# CTLR.net
KiCad netlist of a schematic drawn in Altium Designer
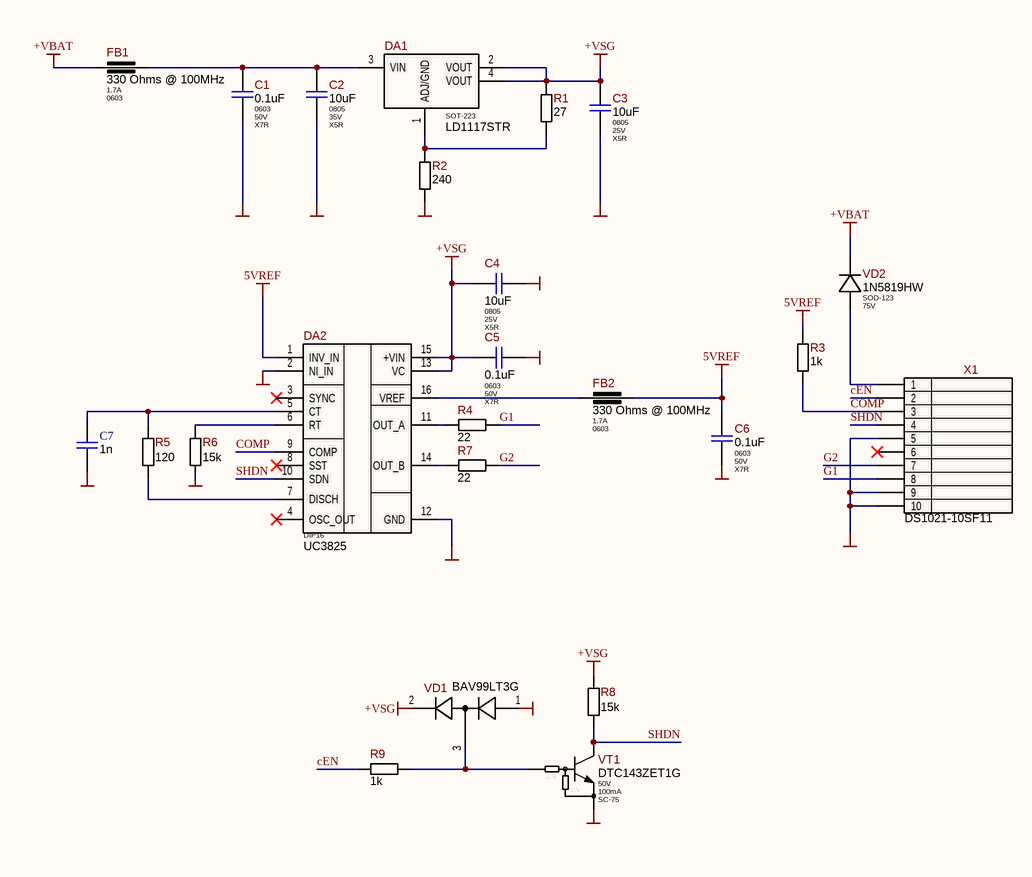
[diagram p0: CTLR.SchDoc]

(export (version "E")
  (design (tool "Eeschema 10.0.6"))
  (components
    (comp (ref "C1")
      (value "0.1uF")
      (footprint "C_CERAMIC_0603_MED")
      (description "100nF 50V X7R ±10% 0603 Ceramic Capacitor RoHS")
      (fields
        (field (name "PACKAGE") "0603")
        (field (name "VOLTAGE") "50V")
        (field (name "DIELECTRIC TYPE") "X7R")
        (field (name "PART NUMBER") "CL10B104KB8NNNC")
        (field (name "MANUFACTURER") "Samsung Electro-Mechanics")
      )
      (libsource (lib "capacitors") (part "CL10B104KB8NNNC"))
    )
    (comp (ref "C2")
      (value "10uF")
      (footprint "CAP-0805(2012)X125T20")
      (description "10uF 35V X5R ±10% 0805 Low ESL Ceramic Capacitor RoHS")
      (fields
        (field (name "PACKAGE") "0805")
        (field (name "VOLTAGE") "35V")
        (field (name "DIELECTRIC TYPE") "X5R")
        (field (name "PART NUMBER") "C2012X5R1V106K125AC")
        (field (name "MANUFACTURER") "TDK Corporation")
      )
      (libsource (lib "capacitors") (part "C2012X5R1V106K125AC"))
    )
    (comp (ref "C3")
      (value "10uF")
      (footprint "CAP-0805(2012)X85T10")
      (description "10uF 25V X5R ±20% 0805 Ceramic Capacitor RoHS")
      (fields
        (field (name "PACKAGE") "0805")
        (field (name "VOLTAGE") "25V")
        (field (name "DIELECTRIC TYPE") "X5R")
        (field (name "PART NUMBER") "C2012X5R1E106M085AC")
        (field (name "MANUFACTURER") "TDK Corporation")
      )
      (libsource (lib "capacitors") (part "C2012X5R1E106M085AC"))
    )
    (comp (ref "C4")
      (value "10uF")
      (footprint "CAP-0805(2012)X85T10")
      (description "10uF 25V X5R ±20% 0805 Ceramic Capacitor RoHS")
      (fields
        (field (name "PACKAGE") "0805")
        (field (name "VOLTAGE") "25V")
        (field (name "DIELECTRIC TYPE") "X5R")
        (field (name "PART NUMBER") "C2012X5R1E106M085AC")
        (field (name "MANUFACTURER") "TDK Corporation")
      )
      (libsource (lib "capacitors") (part "C2012X5R1E106M085AC"))
    )
    (comp (ref "C5")
      (value "0.1uF")
      (footprint "C_CERAMIC_0603_MED")
      (description "100nF 50V X7R ±10% 0603 Ceramic Capacitor RoHS")
      (fields
        (field (name "PACKAGE") "0603")
        (field (name "VOLTAGE") "50V")
        (field (name "DIELECTRIC TYPE") "X7R")
        (field (name "PART NUMBER") "CL10B104KB8NNNC")
        (field (name "MANUFACTURER") "Samsung Electro-Mechanics")
      )
      (libsource (lib "capacitors") (part "CL10B104KB8NNNC"))
    )
    (comp (ref "C6")
      (value "0.1uF")
      (footprint "C_CERAMIC_0603_MED")
      (description "100nF 50V X7R ±10% 0603 Ceramic Capacitor RoHS")
      (fields
        (field (name "PACKAGE") "0603")
        (field (name "VOLTAGE") "50V")
        (field (name "DIELECTRIC TYPE") "X7R")
        (field (name "PART NUMBER") "CL10B104KB8NNNC")
        (field (name "MANUFACTURER") "Samsung Electro-Mechanics")
      )
      (libsource (lib "capacitors") (part "CL10B104KB8NNNC"))
    )
    (comp (ref "C7")
      (value "1n")
      (footprint "CAP: MKS2 (W=2.50MM)")
      (description "Multilayer Ceramic Capacitors MLCC - SMD/SMT 10 uF 25 VDC 10% 1206 X7R")
      (fields (field (name "MANUFACTURER") "Murata") (field (name "PART NUMBER") "GRM31CR71E106KA12L"))
      (libsource (lib "vitech_capacitors") (part "CAP_NON_POLAR_THT"))
    )
    (comp (ref "DA1")
      (value "LD1117STR")
      (footprint "SOT-223")
      (description "Adjustable Low Drop Positive Voltage Regulator, 1.25V to 15V, 800mA")
      (fields
        (field (name "PACKAGE") "SOT-223")
        (field (name "PART NUMBER") "LD1117STR")
        (field (name "MANUFACTURER") "STMicroelectronics")
      )
      (libsource (lib "ic") (part "LD1117STR"))
    )
    (comp (ref "DA2")
      (value "UC3525")
      (footprint "SOIC-16")
      (fields
        (field (name "MANUFACTURER") "Texas")
        (field (name "PACKAGE") "DIP16")
        (field (name "PART NUMBER") "UC3825")
      )
      (libsource (lib "vitech_ic") (part "UC3525"))
    )
    (comp (ref "FB1")
      (value "330 Ohms @ 100MHz")
      (footprint "BLM18-Series_H80T15")
      (description "330 Ohms @ 100 MHz Power Line Ferrite Bead 0603, 1.7A 80mOhm")
      (fields
        (field (name "CURRENT") "1.7A")
        (field (name "PACKAGE") "0603")
        (field (name "PART NUMBER") "BLM18KG331SH1D")
        (field (name "TOLERANCE") "±25%")
      )
      (libsource (lib "inductors") (part "BLM18KG331SH1D"))
    )
    (comp (ref "FB2")
      (value "330 Ohms @ 100MHz")
      (footprint "BLM18-Series_H80T15")
      (description "330 Ohms @ 100 MHz Power Line Ferrite Bead 0603, 1.7A 80mOhm")
      (fields
        (field (name "CURRENT") "1.7A")
        (field (name "PACKAGE") "0603")
        (field (name "PART NUMBER") "BLM18KG331SH1D")
        (field (name "TOLERANCE") "±25%")
      )
      (libsource (lib "inductors") (part "BLM18KG331SH1D"))
    )
    (comp (ref "R1")
      (value "27")
      (footprint "R_ANY_CHIP_0805_MED")
      (description "22 Ohms ±5%, 1/8W 0805 Thick Film Resistor")
      (fields (field (name "TOLERANCE") "±5%") (field (name "PART NUMBER") "RC0805JR-0722RL"))
      (libsource (lib "resistors") (part "RC0805JR-0722RL"))
    )
    (comp (ref "R2")
      (value "240")
      (footprint "R_ANY_CHIP_0805_MED")
      (description "22 Ohms ±5%, 1/8W 0805 Thick Film Resistor")
      (fields (field (name "TOLERANCE") "±5%") (field (name "PART NUMBER") "RC0805JR-0722RL"))
      (libsource (lib "resistors") (part "RC0805JR-0722RL"))
    )
    (comp (ref "R3")
      (value "1k")
      (footprint "R_ANY_CHIP_0805_MED")
      (description "22 Ohms ±5%, 1/8W 0805 Thick Film Resistor")
      (fields (field (name "TOLERANCE") "±5%") (field (name "PART NUMBER") "RC0805JR-0722RL"))
      (libsource (lib "resistors") (part "RC0805JR-0722RL"))
    )
    (comp (ref "R4")
      (value "22")
      (footprint "R_ANY_CHIP_0805_MED")
      (description "22 Ohms ±5%, 1/8W 0805 Thick Film Resistor")
      (fields (field (name "TOLERANCE") "±5%") (field (name "PART NUMBER") "RC0805JR-0722RL"))
      (libsource (lib "resistors") (part "RC0805JR-0722RL"))
    )
    (comp (ref "R5")
      (value "120")
      (footprint "R_ANY_CHIP_0805_MED")
      (description "22 Ohms ±5%, 1/8W 0805 Thick Film Resistor")
      (fields (field (name "TOLERANCE") "±5%") (field (name "PART NUMBER") "RC0805JR-0722RL"))
      (libsource (lib "resistors") (part "RC0805JR-0722RL"))
    )
    (comp (ref "R6")
      (value "15k")
      (footprint "R_ANY_CHIP_0805_MED")
      (description "22 Ohms ±5%, 1/8W 0805 Thick Film Resistor")
      (fields (field (name "TOLERANCE") "±5%") (field (name "PART NUMBER") "RC0805JR-0722RL"))
      (libsource (lib "resistors") (part "RC0805JR-0722RL"))
    )
    (comp (ref "R7")
      (value "22")
      (footprint "R_ANY_CHIP_0805_MED")
      (description "22 Ohms ±5%, 1/8W 0805 Thick Film Resistor")
      (fields (field (name "TOLERANCE") "±5%") (field (name "PART NUMBER") "RC0805JR-0722RL"))
      (libsource (lib "resistors") (part "RC0805JR-0722RL"))
    )
    (comp (ref "R8")
      (value "15k")
      (footprint "R_ANY_CHIP_0805_MED")
      (description "22 Ohms ±5%, 1/8W 0805 Thick Film Resistor")
      (fields (field (name "TOLERANCE") "±5%") (field (name "PART NUMBER") "RC0805JR-0722RL"))
      (libsource (lib "resistors") (part "RC0805JR-0722RL"))
    )
    (comp (ref "R9")
      (value "1k")
      (footprint "R_ANY_CHIP_0805_MED")
      (description "22 Ohms ±5%, 1/8W 0805 Thick Film Resistor")
      (fields (field (name "TOLERANCE") "±5%") (field (name "PART NUMBER") "RC0805JR-0722RL"))
      (libsource (lib "resistors") (part "RC0805JR-0722RL"))
    )
    (comp (ref "VD1")
      (value "BAV99LT3G")
      (footprint "SOT-23_MED")
      (description "Diode Array 1 Pair Series Connection, Standard, 100V, 215mA (DC), SOT-23")
      (fields
        (field (name "VOLTAGE") "100V")
        (field (name "PART NUMBER") "BAV99LT3G")
        (field (name "MANUFACTURER") "Onsemi")
      )
      (libsource (lib "diodes") (part "BAV99LT3G"))
    )
    (comp (ref "VD2")
      (value "1N5819HW")
      (footprint "SOD-123_MED")
      (description "Diode Standart 75V 215mA, SOD-123")
      (fields
        (field (name "PART NUMBER") "1N5819HW")
        (field (name "PACKAGE") "SOD-123")
        (field (name "VOLTAGE") "75V")
        (field (name "MANUFACTURER") "Nexperia USA")
      )
      (libsource (lib "diodes") (part "BAS116GWJ"))
    )
    (comp (ref "VT1")
      (value "DTC143ZET1G")
      (footprint "SOT-416")
      (description "50V, 100mA Low Vce(sat) NPN Digital Transistor, Pre-Biased 4.7k/47k (with built-in resistors)")
      (fields
        (field (name "PART NUMBER") "DTC143ZET1G")
        (field (name "VCE") "50V")
        (field (name "IC") "100mA")
        (field (name "PACKAGE") "SC-75")
        (field (name "MANUFACTURER") "Onsemi")
      )
      (libsource (lib "transistors") (part "DTC143ZET1G"))
    )
    (comp (ref "X1")
      (value "PLS-10 (Part of PLS-40)")
      (footprint "DS1021-10S")
      (description "10 Pin 2.54mm Male Header, Vertical, 3mm and 6.1mm, PLS-5")
      (fields (field (name "PART NUMBER") "DS1021-10SF11") (field (name "MANUFACTURER") "Connfly"))
      (libsource (lib "connectors") (part "DS1021-10SF11"))
    )
  )
  (nets
    (net (code "1") (name "+VBAT") (class "Default")
      (node (ref "FB1") (pin "1") (pintype "passive"))
      (node (ref "VD2") (pin "CA") (pintype "passive"))
    )
    (net (code "2") (name "+VSG") (class "Default")
      (node (ref "C3") (pin "1") (pinfunction "1_1") (pintype "passive"))
      (node (ref "C4") (pin "1") (pinfunction "1_1") (pintype "passive"))
      (node (ref "C5") (pin "1") (pinfunction "1_1") (pintype "passive"))
      (node (ref "DA1") (pin "2") (pinfunction "VOUT_2") (pintype "passive"))
      (node (ref "DA1") (pin "4") (pinfunction "VOUT_4") (pintype "passive"))
      (node (ref "DA2") (pin "13") (pinfunction "VC_13") (pintype "passive"))
      (node (ref "DA2") (pin "15") (pinfunction "+VIN_15") (pintype "passive"))
      (node (ref "R1") (pin "2") (pintype "passive"))
      (node (ref "R8") (pin "2") (pintype "passive"))
      (node (ref "VD1") (pin "2") (pintype "passive"))
    )
    (net (code "3") (name "/COMP") (class "Default")
      (node (ref "DA2") (pin "9") (pinfunction "COMP_9") (pintype "passive"))
      (node (ref "R3") (pin "1") (pintype "passive"))
      (node (ref "X1") (pin "3") (pinfunction "3_3") (pintype "passive"))
    )
    (net (code "4") (name "/G1") (class "Default")
      (node (ref "R4") (pin "2") (pintype "passive"))
      (node (ref "X1") (pin "8") (pinfunction "8_8") (pintype "passive"))
    )
    (net (code "5") (name "/G2") (class "Default")
      (node (ref "R7") (pin "2") (pintype "passive"))
      (node (ref "X1") (pin "7") (pinfunction "7_7") (pintype "passive"))
    )
    (net (code "6") (name "/SHDN") (class "Default")
      (node (ref "DA2") (pin "10") (pinfunction "SDN_10") (pintype "passive"))
      (node (ref "R8") (pin "1") (pintype "passive"))
      (node (ref "VT1") (pin "3") (pinfunction "C_3") (pintype "passive"))
      (node (ref "X1") (pin "4") (pinfunction "4_4") (pintype "passive"))
    )
    (net (code "7") (name "/cEN") (class "Default")
      (node (ref "R9") (pin "2") (pintype "passive"))
      (node (ref "X1") (pin "2") (pinfunction "2_2") (pintype "passive"))
    )
    (net (code "8") (name "5VREF") (class "Default")
      (node (ref "C6") (pin "2") (pinfunction "2_2") (pintype "passive"))
      (node (ref "DA2") (pin "1") (pinfunction "INV_IN_1") (pintype "passive"))
      (node (ref "FB2") (pin "2") (pintype "passive"))
      (node (ref "R3") (pin "2") (pintype "passive"))
    )
    (net (code "9") (name "GND") (class "Default")
      (node (ref "C1") (pin "2") (pinfunction "2_2") (pintype "passive"))
      (node (ref "C2") (pin "2") (pinfunction "2_2") (pintype "passive"))
      (node (ref "C3") (pin "2") (pinfunction "2_2") (pintype "passive"))
      (node (ref "C4") (pin "2") (pinfunction "2_2") (pintype "passive"))
      (node (ref "C5") (pin "2") (pinfunction "2_2") (pintype "passive"))
      (node (ref "C6") (pin "1") (pinfunction "1_1") (pintype "passive"))
      (node (ref "C7") (pin "1") (pinfunction "1_1") (pintype "passive"))
      (node (ref "DA2") (pin "12") (pinfunction "GND_12") (pintype "passive"))
      (node (ref "DA2") (pin "2") (pinfunction "NI_IN_2") (pintype "passive"))
      (node (ref "R2") (pin "1") (pintype "passive"))
      (node (ref "R6") (pin "1") (pintype "passive"))
      (node (ref "VD1") (pin "1") (pintype "passive"))
      (node (ref "VT1") (pin "2") (pinfunction "E_2") (pintype "passive"))
      (node (ref "X1") (pin "10") (pinfunction "10_10") (pintype "passive"))
      (node (ref "X1") (pin "5") (pinfunction "5_5") (pintype "passive"))
      (node (ref "X1") (pin "9") (pinfunction "9_9") (pintype "passive"))
    )
    (net (code "10") (name "Net-(DA1-ADJ{slash}GND)") (class "Default")
      (node (ref "DA1") (pin "1") (pinfunction "ADJ/GND_1") (pintype "passive"))
      (node (ref "R1") (pin "1") (pintype "passive"))
      (node (ref "R2") (pin "2") (pintype "passive"))
    )
    (net (code "11") (name "Net-(DA1-VIN)") (class "Default")
      (node (ref "C1") (pin "1") (pinfunction "1_1") (pintype "passive"))
      (node (ref "C2") (pin "1") (pinfunction "1_1") (pintype "passive"))
      (node (ref "DA1") (pin "3") (pinfunction "VIN_3") (pintype "passive"))
      (node (ref "FB1") (pin "2") (pintype "passive"))
    )
    (net (code "12") (name "Net-(DA2-CT)") (class "Default")
      (node (ref "C7") (pin "2") (pinfunction "2_2") (pintype "passive"))
      (node (ref "DA2") (pin "5") (pinfunction "CT_5") (pintype "passive"))
      (node (ref "R5") (pin "2") (pintype "passive"))
    )
    (net (code "13") (name "Net-(DA2-DISCH)") (class "Default")
      (node (ref "DA2") (pin "7") (pinfunction "DISCH_7") (pintype "passive"))
      (node (ref "R5") (pin "1") (pintype "passive"))
    )
    (net (code "14") (name "Net-(DA2-OUT_A)") (class "Default")
      (node (ref "DA2") (pin "11") (pinfunction "OUT_A_11") (pintype "passive"))
      (node (ref "R4") (pin "1") (pintype "passive"))
    )
    (net (code "15") (name "Net-(DA2-OUT_B)") (class "Default")
      (node (ref "DA2") (pin "14") (pinfunction "OUT_B_14") (pintype "passive"))
      (node (ref "R7") (pin "1") (pintype "passive"))
    )
    (net (code "16") (name "Net-(DA2-RT)") (class "Default")
      (node (ref "DA2") (pin "6") (pinfunction "RT_6") (pintype "passive"))
      (node (ref "R6") (pin "2") (pintype "passive"))
    )
    (net (code "17") (name "Net-(DA2-VREF)") (class "Default")
      (node (ref "DA2") (pin "16") (pinfunction "VREF_16") (pintype "passive"))
      (node (ref "FB2") (pin "1") (pintype "passive"))
    )
    (net (code "18") (name "Net-(VD2-PadAN)") (class "Default")
      (node (ref "VD2") (pin "AN") (pintype "passive"))
      (node (ref "X1") (pin "1") (pinfunction "1_1") (pintype "passive"))
    )
    (net (code "19") (name "Net-(VT1-B)") (class "Default")
      (node (ref "R9") (pin "1") (pintype "passive"))
      (node (ref "VD1") (pin "3") (pintype "passive"))
      (node (ref "VT1") (pin "1") (pinfunction "B_1") (pintype "passive"))
    )
    (net (code "20") (name "unconnected-(DA2-OSC_OUT-Pad4)") (class "Default")
      (node (ref "DA2") (pin "4") (pinfunction "OSC_OUT_4") (pintype "passive+no_connect"))
    )
    (net (code "21") (name "unconnected-(DA2-SST-Pad8)") (class "Default")
      (node (ref "DA2") (pin "8") (pinfunction "SST_8") (pintype "passive+no_connect"))
    )
    (net (code "22") (name "unconnected-(DA2-SYNC-Pad3)") (class "Default")
      (node (ref "DA2") (pin "3") (pinfunction "SYNC_3") (pintype "passive+no_connect"))
    )
    (net (code "23") (name "unconnected-(X1-Pad6)") (class "Default")
      (node (ref "X1") (pin "6") (pinfunction "6_6") (pintype "passive+no_connect"))
    )
  )
)
